# HB-OU-MP3-LED_V1_0.net
KiCad netlist of a schematic drawn in EAGLE
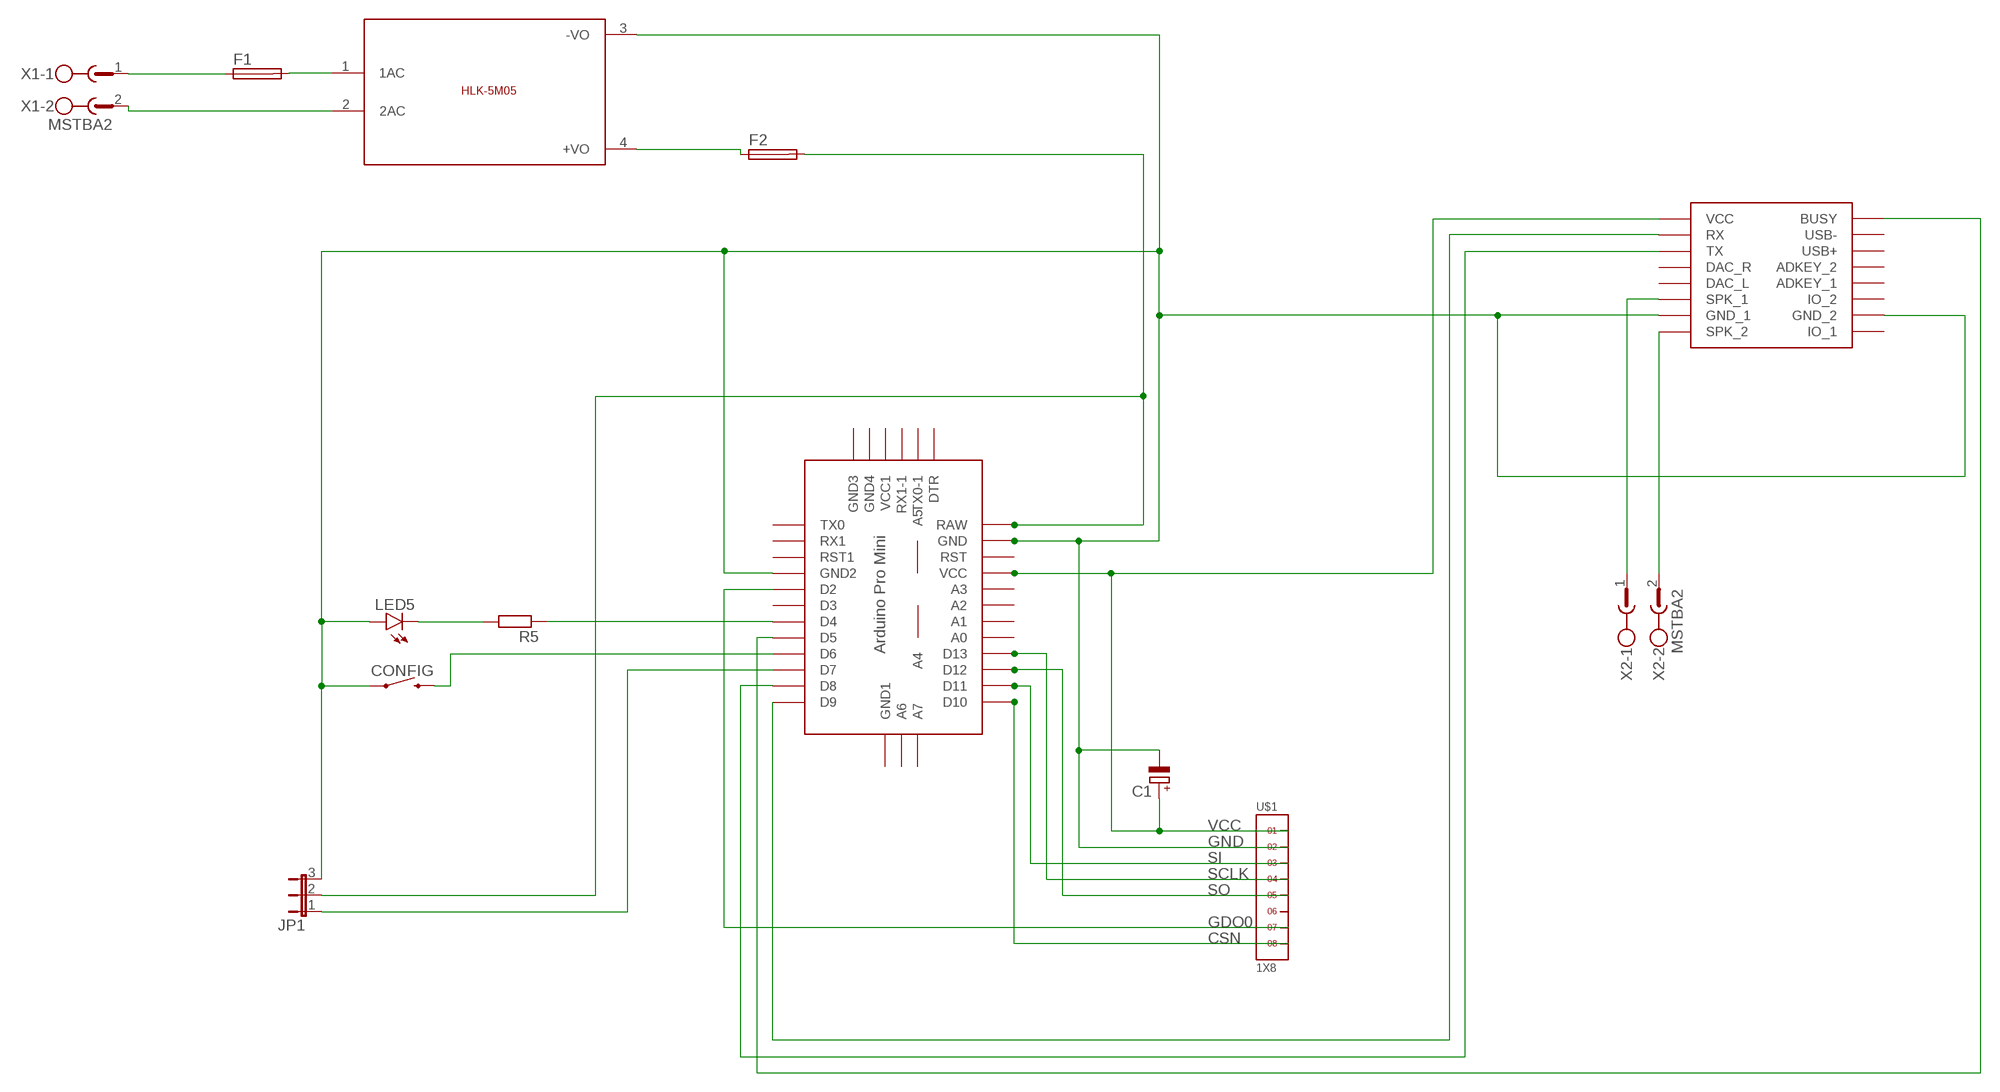
[diagram p0: schematic, sheet 1]

(export (version "E")
  (design (tool "Eeschema 10.0.6"))
  (components
    (comp (ref "C1")
      (value "CPOL-EUE2.5-5")
      (footprint "eagle-import:E2,5-5")
      (libsource (lib "eagle-import") (part "CPOL-EUE2.5-5"))
    )
    (comp (ref "CONFIG")
      (value "MOMENTARY-SWITCH-SPST-PTH-6.0MM-KIT")
      (footprint "eagle-import:TACTILE_SWITCH_PTH_6.0MM_KIT")
      (libsource (lib "eagle-import") (part "MOMENTARY-SWITCH-SPST-PTH-6.0MM-KIT"))
    )
    (comp (ref "F1")
      (value "SH22,5A")
      (footprint "eagle-import:SH22,5A")
      (fields (field (name "MPN") "0031.7701.11"))
      (libsource (lib "eagle-import") (part "SH22,5A"))
    )
    (comp (ref "F2")
      (value "SH22,5A")
      (footprint "eagle-import:SH22,5A")
      (fields (field (name "MPN") "0031.7701.11"))
      (libsource (lib "eagle-import") (part "SH22,5A"))
    )
    (comp (ref "JP1")
      (value "JP2E")
      (footprint "eagle-import:JP2")
      (libsource (lib "eagle-import") (part "JP2E"))
    )
    (comp (ref "LED5")
      (value "LED3MM")
      (footprint "eagle-import:LED3MM")
      (libsource (lib "eagle-import") (part "LED3MM"))
    )
    (comp (ref "R5")
      (value "R-EU_0309/10")
      (footprint "eagle-import:0309_10")
      (libsource (lib "eagle-import") (part "R-EU_0309/10"))
    )
    (comp (ref "U$1")
      (value "1X8")
      (footprint "eagle-import:1X8")
      (libsource (lib "eagle-import") (part "1X8"))
    )
    (comp (ref "U$2")
      (value "ABK-PRO-MINI")
      (footprint "eagle-import:ABK-PRO-MINI")
      (libsource (lib "eagle-import") (part "ABK-PRO-MINI"))
    )
    (comp (ref "U$3")
      (value "5VDC/5W")
      (footprint "eagle-import:HLK-5M05")
      (libsource (lib "eagle-import") (part "HLK-5M05"))
    )
    (comp (ref "U$4")
      (value "DFPLAYER")
      (footprint "eagle-import:DFPLAYER")
      (libsource (lib "eagle-import") (part "DFPLAYER"))
    )
    (comp (ref "X1")
      (value "MSTBA2")
      (footprint "eagle-import:MSTBA2")
      (fields (field (name "MF") "FARNELL") (field (name "MPN") "1757242"))
      (libsource (lib "eagle-import") (part "MSTBA2"))
    )
    (comp (ref "X2")
      (value "MSTBA2")
      (footprint "eagle-import:MSTBA2")
      (fields (field (name "MF") "FARNELL") (field (name "MPN") "1757242"))
      (libsource (lib "eagle-import") (part "MSTBA2"))
    )
  )
  (nets
    (net (code "1") (name "/CSN") (class "Default")
      (node (ref "U$1") (pin "8") (pinfunction "8_8") (pintype "bidirectional"))
      (node (ref "U$2") (pin "D10") (pinfunction "D10_D10") (pintype "bidirectional"))
    )
    (net (code "2") (name "/GDO0") (class "Default")
      (node (ref "U$1") (pin "7") (pinfunction "7_7") (pintype "bidirectional"))
      (node (ref "U$2") (pin "D2") (pinfunction "D2_D2") (pintype "bidirectional"))
    )
    (net (code "3") (name "/GND") (class "Default")
      (node (ref "C1") (pin "-") (pinfunction "-_-") (pintype "passive"))
      (node (ref "CONFIG") (pin "1") (pinfunction "1_1") (pintype "passive"))
      (node (ref "JP1") (pin "3") (pinfunction "3_3") (pintype "passive"))
      (node (ref "LED5") (pin "A") (pinfunction "A_A") (pintype "passive"))
      (node (ref "U$1") (pin "2") (pinfunction "2_2") (pintype "bidirectional"))
      (node (ref "U$2") (pin "GND") (pinfunction "GND_GND") (pintype "bidirectional"))
      (node (ref "U$2") (pin "GND1") (pinfunction "GND2_GND1") (pintype "bidirectional"))
      (node (ref "U$3") (pin "3") (pinfunction "-VO_3") (pintype "bidirectional"))
      (node (ref "U$4") (pin "GND_1") (pinfunction "GND_1_GND_1") (pintype "bidirectional"))
      (node (ref "U$4") (pin "GND_2") (pinfunction "GND_2_GND_2") (pintype "bidirectional"))
    )
    (net (code "4") (name "/SCLK") (class "Default")
      (node (ref "U$1") (pin "4") (pinfunction "4_4") (pintype "bidirectional"))
      (node (ref "U$2") (pin "D13") (pinfunction "D13_D13") (pintype "bidirectional"))
    )
    (net (code "5") (name "/SI") (class "Default")
      (node (ref "U$1") (pin "3") (pinfunction "3_3") (pintype "bidirectional"))
      (node (ref "U$2") (pin "D11") (pinfunction "D11_D11") (pintype "bidirectional"))
    )
    (net (code "6") (name "/SO") (class "Default")
      (node (ref "U$1") (pin "5") (pinfunction "5_5") (pintype "bidirectional"))
      (node (ref "U$2") (pin "D12") (pinfunction "D12_D12") (pintype "bidirectional"))
    )
    (net (code "7") (name "/VCC") (class "Default")
      (node (ref "C1") (pin "+") (pinfunction "+_+") (pintype "passive"))
      (node (ref "U$1") (pin "1") (pinfunction "1_1") (pintype "bidirectional"))
      (node (ref "U$2") (pin "VCC") (pinfunction "VCC_VCC") (pintype "bidirectional"))
      (node (ref "U$4") (pin "VCC") (pinfunction "VCC_VCC") (pintype "bidirectional"))
    )
    (net (code "8") (name "Net-(CONFIG-2)") (class "Default")
      (node (ref "CONFIG") (pin "3") (pinfunction "2_3") (pintype "passive"))
      (node (ref "U$2") (pin "D6") (pinfunction "D6_D6") (pintype "bidirectional"))
    )
    (net (code "9") (name "Net-(F1-Pad1)") (class "Default")
      (node (ref "F1") (pin "1") (pinfunction "1_1") (pintype "passive"))
      (node (ref "X1") (pin "1") (pinfunction "1_1") (pintype "passive"))
    )
    (net (code "10") (name "Net-(F2-Pad2)") (class "Default")
      (node (ref "F2") (pin "2") (pinfunction "2_2") (pintype "passive"))
      (node (ref "JP1") (pin "2") (pinfunction "2_2") (pintype "passive"))
      (node (ref "U$2") (pin "RAW") (pinfunction "RAW_RAW") (pintype "bidirectional"))
    )
    (net (code "11") (name "Net-(JP1-Pad1)") (class "Default")
      (node (ref "JP1") (pin "1") (pinfunction "1_1") (pintype "passive"))
      (node (ref "U$2") (pin "D7") (pinfunction "D7_D7") (pintype "bidirectional"))
    )
    (net (code "12") (name "Net-(LED5-C)") (class "Default")
      (node (ref "LED5") (pin "K") (pinfunction "C_K") (pintype "passive"))
      (node (ref "R5") (pin "2") (pinfunction "2_2") (pintype "passive"))
    )
    (net (code "13") (name "Net-(R5-Pad1)") (class "Default")
      (node (ref "R5") (pin "1") (pinfunction "1_1") (pintype "passive"))
      (node (ref "U$2") (pin "D4") (pinfunction "D4_D4") (pintype "bidirectional"))
    )
    (net (code "14") (name "Net-(U$2-PadD5)") (class "Default")
      (node (ref "U$2") (pin "D5") (pinfunction "D5_D5") (pintype "bidirectional"))
      (node (ref "U$4") (pin "BUSY") (pinfunction "BUSY_BUSY") (pintype "bidirectional"))
    )
    (net (code "15") (name "Net-(U$2-PadD8)") (class "Default")
      (node (ref "U$2") (pin "D8") (pinfunction "D8_D8") (pintype "bidirectional"))
      (node (ref "U$4") (pin "TX") (pinfunction "TX_TX") (pintype "bidirectional"))
    )
    (net (code "16") (name "Net-(U$2-PadD9)") (class "Default")
      (node (ref "U$2") (pin "D9") (pinfunction "D9_D9") (pintype "bidirectional"))
      (node (ref "U$4") (pin "RX") (pinfunction "RX_RX") (pintype "bidirectional"))
    )
    (net (code "17") (name "Net-(U$3-+VO)") (class "Default")
      (node (ref "F2") (pin "1") (pinfunction "1_1") (pintype "passive"))
      (node (ref "U$3") (pin "4") (pinfunction "+VO_4") (pintype "bidirectional"))
    )
    (net (code "18") (name "Net-(U$3-1AC)") (class "Default")
      (node (ref "F1") (pin "2") (pinfunction "2_2") (pintype "passive"))
      (node (ref "U$3") (pin "1") (pinfunction "1AC_1") (pintype "bidirectional"))
    )
    (net (code "19") (name "Net-(U$3-2AC)") (class "Default")
      (node (ref "U$3") (pin "2") (pinfunction "2AC_2") (pintype "bidirectional"))
      (node (ref "X1") (pin "2") (pinfunction "1_2") (pintype "passive"))
    )
    (net (code "20") (name "Net-(U$4-SPK_1)") (class "Default")
      (node (ref "U$4") (pin "SPK1") (pinfunction "SPK_1_SPK1") (pintype "bidirectional"))
      (node (ref "X2") (pin "1") (pinfunction "1_1") (pintype "passive"))
    )
    (net (code "21") (name "Net-(U$4-SPK_2)") (class "Default")
      (node (ref "U$4") (pin "SPK2") (pinfunction "SPK_2_SPK2") (pintype "bidirectional"))
      (node (ref "X2") (pin "2") (pinfunction "1_2") (pintype "passive"))
    )
    (net (code "22") (name "unconnected-(U$1-Pad6)") (class "Default")
      (node (ref "U$1") (pin "6") (pinfunction "6_6") (pintype "bidirectional"))
    )
    (net (code "23") (name "unconnected-(U$2-GND1-PadGND4)") (class "Default")
      (node (ref "U$2") (pin "GND4") (pinfunction "GND1_GND4") (pintype "bidirectional"))
    )
    (net (code "24") (name "unconnected-(U$2-GND3-PadGND2)") (class "Default")
      (node (ref "U$2") (pin "GND2") (pinfunction "GND3_GND2") (pintype "bidirectional"))
    )
    (net (code "25") (name "unconnected-(U$2-GND4-PadGND3)") (class "Default")
      (node (ref "U$2") (pin "GND3") (pinfunction "GND4_GND3") (pintype "bidirectional"))
    )
    (net (code "26") (name "unconnected-(U$2-PadA0)") (class "Default")
      (node (ref "U$2") (pin "A0") (pinfunction "A0_A0") (pintype "bidirectional"))
    )
    (net (code "27") (name "unconnected-(U$2-PadA1)") (class "Default")
      (node (ref "U$2") (pin "A1") (pinfunction "A1_A1") (pintype "bidirectional"))
    )
    (net (code "28") (name "unconnected-(U$2-PadA2)") (class "Default")
      (node (ref "U$2") (pin "A2") (pinfunction "A2_A2") (pintype "bidirectional"))
    )
    (net (code "29") (name "unconnected-(U$2-PadA3)") (class "Default")
      (node (ref "U$2") (pin "A3") (pinfunction "A3_A3") (pintype "bidirectional"))
    )
    (net (code "30") (name "unconnected-(U$2-PadA4)") (class "Default")
      (node (ref "U$2") (pin "A4") (pinfunction "A4_A4") (pintype "bidirectional"))
    )
    (net (code "31") (name "unconnected-(U$2-PadA5)") (class "Default")
      (node (ref "U$2") (pin "A5") (pinfunction "A5_A5") (pintype "bidirectional"))
    )
    (net (code "32") (name "unconnected-(U$2-PadA6)") (class "Default")
      (node (ref "U$2") (pin "A6") (pinfunction "A6_A6") (pintype "bidirectional"))
    )
    (net (code "33") (name "unconnected-(U$2-PadA7)") (class "Default")
      (node (ref "U$2") (pin "A7") (pinfunction "A7_A7") (pintype "bidirectional"))
    )
    (net (code "34") (name "unconnected-(U$2-PadD3)") (class "Default")
      (node (ref "U$2") (pin "D3") (pinfunction "D3_D3") (pintype "bidirectional"))
    )
    (net (code "35") (name "unconnected-(U$2-PadDTR)") (class "Default")
      (node (ref "U$2") (pin "DTR") (pinfunction "DTR_DTR") (pintype "bidirectional"))
    )
    (net (code "36") (name "unconnected-(U$2-PadRST)") (class "Default")
      (node (ref "U$2") (pin "RST") (pinfunction "RST_RST") (pintype "bidirectional"))
    )
    (net (code "37") (name "unconnected-(U$2-PadRST1)") (class "Default")
      (node (ref "U$2") (pin "RST1") (pinfunction "RST1_RST1") (pintype "bidirectional"))
    )
    (net (code "38") (name "unconnected-(U$2-PadRX1)") (class "Default")
      (node (ref "U$2") (pin "RX1") (pinfunction "RX1_RX1") (pintype "bidirectional"))
    )
    (net (code "39") (name "unconnected-(U$2-PadRX1-1)") (class "Default")
      (node (ref "U$2") (pin "RX1-1") (pinfunction "RX1-1_RX1-1") (pintype "bidirectional"))
    )
    (net (code "40") (name "unconnected-(U$2-PadTX0)") (class "Default")
      (node (ref "U$2") (pin "TX0") (pinfunction "TX0_TX0") (pintype "bidirectional"))
    )
    (net (code "41") (name "unconnected-(U$2-PadTX0-1)") (class "Default")
      (node (ref "U$2") (pin "TX0-1") (pinfunction "TX0-1_TX0-1") (pintype "bidirectional"))
    )
    (net (code "42") (name "unconnected-(U$2-PadVCC1)") (class "Default")
      (node (ref "U$2") (pin "VCC1") (pinfunction "VCC1_VCC1") (pintype "bidirectional"))
    )
    (net (code "43") (name "unconnected-(U$4-ADKEY_1-PadADKEY1)") (class "Default")
      (node (ref "U$4") (pin "ADKEY1") (pinfunction "ADKEY_1_ADKEY1") (pintype "bidirectional"))
    )
    (net (code "44") (name "unconnected-(U$4-ADKEY_2-PadADKEY2)") (class "Default")
      (node (ref "U$4") (pin "ADKEY2") (pinfunction "ADKEY_2_ADKEY2") (pintype "bidirectional"))
    )
    (net (code "45") (name "unconnected-(U$4-IO_1-PadIO1)") (class "Default")
      (node (ref "U$4") (pin "IO1") (pinfunction "IO_1_IO1") (pintype "bidirectional"))
    )
    (net (code "46") (name "unconnected-(U$4-IO_2-PadIO2)") (class "Default")
      (node (ref "U$4") (pin "IO2") (pinfunction "IO_2_IO2") (pintype "bidirectional"))
    )
    (net (code "47") (name "unconnected-(U$4-PadDAC_L)") (class "Default")
      (node (ref "U$4") (pin "DAC_L") (pinfunction "DAC_L_DAC_L") (pintype "bidirectional"))
    )
    (net (code "48") (name "unconnected-(U$4-PadDAC_R)") (class "Default")
      (node (ref "U$4") (pin "DAC_R") (pinfunction "DAC_R_DAC_R") (pintype "bidirectional"))
    )
    (net (code "49") (name "unconnected-(U$4-PadUSB+)") (class "Default")
      (node (ref "U$4") (pin "USB+") (pinfunction "USB+_USB+") (pintype "bidirectional"))
    )
    (net (code "50") (name "unconnected-(U$4-PadUSB-)") (class "Default")
      (node (ref "U$4") (pin "USB-") (pinfunction "USB-_USB-") (pintype "bidirectional"))
    )
  )
)
